# Schematic_Rev1.net
KiCad netlist of a schematic drawn in Altium Designer
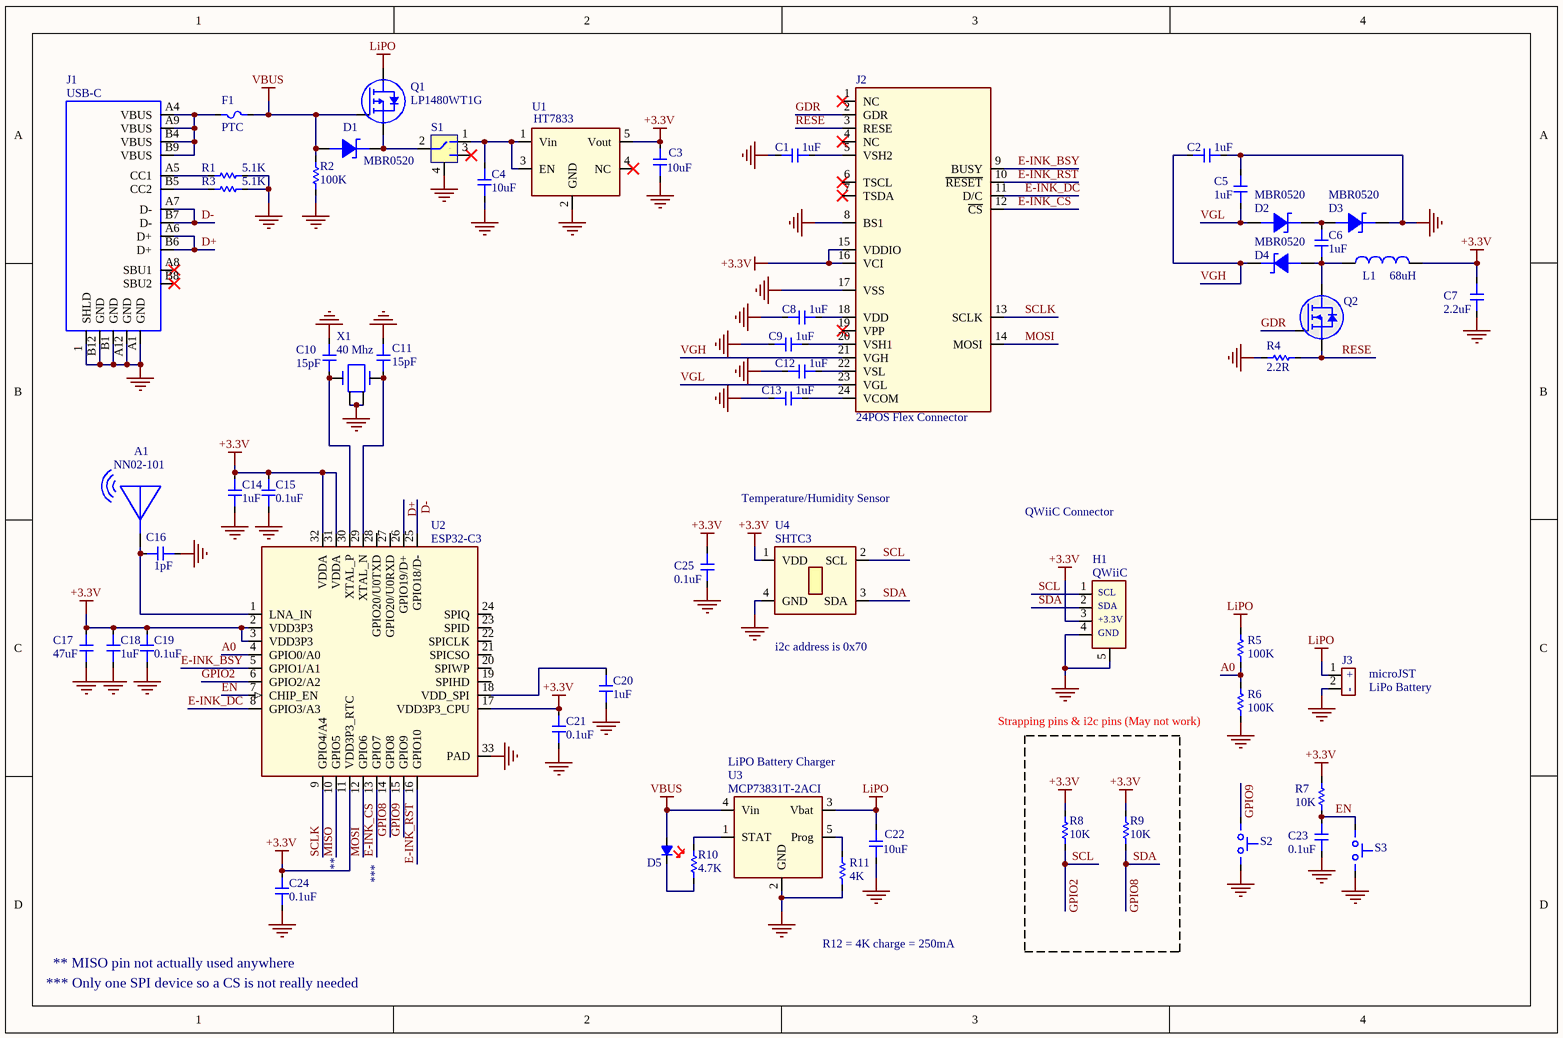
[diagram p0: Schematic_Rev1.SchDoc]

(export (version "E")
  (design (tool "Eeschema 10.0.6"))
  (components
    (comp (ref "A1")
      (value "NN02-101")
      (footprint "NN02-101")
      (description "Antenna Chip 2.4Gig")
      (fields (field (name "MANUFACTURER") "Ignion"))
      (libsource (lib "MAR") (part "NN02-101"))
    )
    (comp (ref "C1")
      (value "1uF")
      (footprint "CAPC1005X56N")
      (description "CAP 1uF 0402")
      (libsource (lib "MAR") (part "CAP_0402"))
    )
    (comp (ref "C2")
      (value "1uF")
      (footprint "CAPC1005X56N")
      (description "CAP 1uF 0402")
      (libsource (lib "MAR") (part "CAP_0402"))
    )
    (comp (ref "C3")
      (value "10uF")
      (footprint "CAPC2012X140N")
      (description "CAP 10uF 0805")
      (libsource (lib "MAR") (part "CAP_0805"))
    )
    (comp (ref "C4")
      (value "10uF")
      (footprint "CAPC2012X140N")
      (description "CAP 10uF 0805")
      (libsource (lib "MAR") (part "CAP_0805"))
    )
    (comp (ref "C5")
      (value "1uF")
      (footprint "CAPC1005X56N")
      (description "CAP 1uF 0402")
      (libsource (lib "MAR") (part "CAP_0402"))
    )
    (comp (ref "C6")
      (value "1uF")
      (footprint "CAPC1005X56N")
      (description "CAP 1uF 0402")
      (libsource (lib "MAR") (part "CAP_0402"))
    )
    (comp (ref "C7")
      (value "2.2uF")
      (footprint "CAPC1608X09L")
      (description "CAP 2.2uF 0603")
      (libsource (lib "MAR") (part "CAP_0402"))
    )
    (comp (ref "C8")
      (value "1uF")
      (footprint "CAPC1005X56N")
      (description "CAP 1uF 0402")
      (libsource (lib "MAR") (part "CAP_0402"))
    )
    (comp (ref "C9")
      (value "1uF")
      (footprint "CAPC1005X56N")
      (description "CAP 1uF 0402")
      (libsource (lib "MAR") (part "CAP_0402"))
    )
    (comp (ref "C10")
      (value "15pF")
      (footprint "CAPC1005X56N")
      (description "CAP 15pF 0402")
      (libsource (lib "MAR") (part "CAP_0402"))
    )
    (comp (ref "C11")
      (value "15pF")
      (footprint "CAPC1005X56N")
      (description "CAP 15pF 0402")
      (libsource (lib "MAR") (part "CAP_0402"))
    )
    (comp (ref "C12")
      (value "1uF")
      (footprint "CAPC1005X56N")
      (description "CAP 1uF 0402")
      (libsource (lib "MAR") (part "CAP_0402"))
    )
    (comp (ref "C13")
      (value "1uF")
      (footprint "CAPC1005X56N")
      (description "CAP 1uF 0402")
      (libsource (lib "MAR") (part "CAP_0402"))
    )
    (comp (ref "C14")
      (value "1uF")
      (footprint "CAPC1005X56N")
      (description "CAP 1uF 0402")
      (libsource (lib "MAR") (part "CAP_0402"))
    )
    (comp (ref "C15")
      (value "0.1uF")
      (footprint "CAPC1005X56N")
      (description "CAP 0.1uF 0402")
      (libsource (lib "MAR") (part "CAP_0402"))
    )
    (comp (ref "C16")
      (value "1pF")
      (footprint "CAPC1005X56N")
      (description "CAP 1pF 0402")
      (libsource (lib "MAR") (part "CAP_0402"))
    )
    (comp (ref "C17")
      (value "47uF")
      (footprint "CAPC3225X160N")
      (description "CAP 47uF 1210")
      (libsource (lib "MAR") (part "CAP_0402"))
    )
    (comp (ref "C18")
      (value "1uF")
      (footprint "CAPC1005X56N")
      (description "CAP 1uF 0402")
      (libsource (lib "MAR") (part "CAP_0402"))
    )
    (comp (ref "C19")
      (value "0.1uF")
      (footprint "CAPC1005X56N")
      (description "CAP 0.1uF 0402")
      (libsource (lib "MAR") (part "CAP_0402"))
    )
    (comp (ref "C20")
      (value "1uF")
      (footprint "CAPC1005X56N")
      (description "CAP 1uF 0402")
      (libsource (lib "MAR") (part "CAP_0402"))
    )
    (comp (ref "C21")
      (value "0.1uF")
      (footprint "CAPC1005X56N")
      (description "CAP 0.1uF 0402")
      (libsource (lib "MAR") (part "CAP_0402"))
    )
    (comp (ref "C22")
      (value "10uF")
      (footprint "CAPC2012X140N")
      (description "CAP 10uF 0805")
      (libsource (lib "MAR") (part "CAP_0805"))
    )
    (comp (ref "C23")
      (value "0.1uF")
      (footprint "CAPC1005X56N")
      (description "CAP 0.1uF 0402")
      (libsource (lib "MAR") (part "CAP_0402"))
    )
    (comp (ref "C24")
      (value "0.1uF")
      (footprint "CAPC1005X56N")
      (description "CAP 0.1uF 0402")
      (libsource (lib "MAR") (part "CAP_0402"))
    )
    (comp (ref "C25")
      (value "0.1uF")
      (footprint "CAPC1005X56N")
      (description "CAP 0.1uF 0402")
      (libsource (lib "MAR") (part "CAP_0402"))
    )
    (comp (ref "D1")
      (value "MBR0520")
      (footprint "SOD123")
      (description "DIODE SCHOTTKY 20V 500MA SOD-123")
      (fields (field (name "MANUFACTURER") "Micro") (field (name "PART_NUMBER") "C78746"))
      (libsource (lib "MAR") (part "MBR0520-TP"))
    )
    (comp (ref "D2")
      (value "MBR0520")
      (footprint "SOD123")
      (description "DIODE SCHOTTKY 20V 500MA SOD-123")
      (fields (field (name "MANUFACTURER") "Micro") (field (name "PART_NUMBER") "C78746"))
      (libsource (lib "MAR") (part "MBR0520-TP"))
    )
    (comp (ref "D3")
      (value "MBR0520")
      (footprint "SOD123")
      (description "DIODE SCHOTTKY 20V 500MA SOD-123")
      (fields (field (name "MANUFACTURER") "Micro") (field (name "PART_NUMBER") "C78746"))
      (libsource (lib "MAR") (part "MBR0520-TP"))
    )
    (comp (ref "D4")
      (value "MBR0520")
      (footprint "SOD123")
      (description "DIODE SCHOTTKY 20V 500MA SOD-123")
      (fields (field (name "MANUFACTURER") "Micro") (field (name "PART_NUMBER") "C78746"))
      (libsource (lib "MAR") (part "MBR0520-TP"))
    )
    (comp (ref "D5")
      (value "Red Led")
      (footprint "LED1005X40N-Red")
      (description "LED Red 0402")
      (fields (field (name "PART_NUMBER") "C364556") (field (name "MANUFACTURER") "Lite-On"))
      (libsource (lib "MAR") (part "LED_0402_SMALL_Red"))
    )
    (comp (ref "F1")
      (value "TLC-PSMD050")
      (footprint "PTC2012X70L")
      (description "PTC FUSE 500mA hold, 1A trip")
      (fields (field (name "MANUFACTURER") "TLC") (field (name "PART_NUMBER") "C261942"))
      (libsource (lib "MAR") (part "PTC_FUSE"))
    )
    (comp (ref "H1")
      (value "QWiiC")
      (footprint "SM04B-SRSS-TB")
      (description "CONN HEADER 4POS .100 R/A QWIIC")
      (fields (field (name "MANUFACTURER") "JST") (field (name "PART_NUMBER") "PRT-14417"))
      (libsource (lib "MAR") (part "SM04B-SRSS-TB"))
    )
    (comp (ref "J1")
      (value "USB-C")
      (footprint "TYPE-C-31-M-12")
      (description "CONN RECPT USB-C")
      (fields (field (name "MANUFACTURER") "KHE") (field (name "PART_NUMBER") "C165948"))
      (libsource (lib "MAR") (part "USB-C"))
    )
    (comp (ref "J2")
      (value "24POS Flex Connector")
      (footprint "687124182122")
      (description "CONN FFC TOP/BOT 24POS 0.50MM R/A")
      (fields (field (name "MANUFACTURER") "Wurth") (field (name "PART_NUMBER") "687124182122"))
      (libsource (lib "MAR") (part "687124182122"))
    )
    (comp (ref "J3")
      (value "CON2")
      (footprint "JST_Micro_2PIN")
      (description "JST MIcro CONN 2POS")
      (libsource (lib "MAR") (part "JST_Micro_CONN_2PIN"))
    )
    (comp (ref "L1")
      (value "68uH")
      (footprint "INDUCTOR, 4mmX4mm")
      (description "INDUCTOR 68uH 20% 4mmx4mm")
      (fields (field (name "PART_NUMBER") "C135265") (field (name "MANUFACTURER") "SXN"))
      (libsource (lib "MAR") (part "68uH"))
    )
    (comp (ref "Q1")
      (value "LP1480WT1G")
      (footprint "SC-70")
      (description "MOSFET P-CH 20V 1.4A SC-70")
      (fields (field (name "MANUFACTURER") "LRC") (field (name "PART_NUMBER") "C172434"))
      (libsource (lib "MAR") (part "LP1480WT1G"))
    )
    (comp (ref "Q2")
      (value "~")
      (footprint "SOT95P240X110-3N")
      (description "MOSFET N-CH 60V 300MA SOT-23")
      (fields (field (name "MANUFACTURER") "Vishay Siliconix") (field (name "PART_NUMBER") "2N7002K-T1-E3"))
      (libsource (lib "MAR") (part "2N7002K-T1-E3"))
    )
    (comp (ref "R1")
      (value "5.1K")
      (footprint "RESC1005X40L (0402 FOOTPRINT)")
      (description "RES 5.1K 0402")
      (libsource (lib "MAR") (part "RES_0402"))
    )
    (comp (ref "R2")
      (value "100K")
      (footprint "RESC1005X40L (0402 FOOTPRINT)")
      (description "RES 100K 0402")
      (libsource (lib "MAR") (part "RES_0402"))
    )
    (comp (ref "R3")
      (value "5.1K")
      (footprint "RESC1005X40L (0402 FOOTPRINT)")
      (description "RES 5.1K 0402")
      (libsource (lib "MAR") (part "RES_0402"))
    )
    (comp (ref "R4")
      (value "2.2R")
      (footprint "RESC1005X40L (0402 FOOTPRINT)")
      (description "RES 2.2R 0402")
      (libsource (lib "MAR") (part "RES_0402"))
    )
    (comp (ref "R5")
      (value "100K")
      (footprint "RESC1005X40L (0402 FOOTPRINT)")
      (description "RES 100K 0402")
      (libsource (lib "MAR") (part "RES_0402"))
    )
    (comp (ref "R6")
      (value "100K")
      (footprint "RESC1005X40L (0402 FOOTPRINT)")
      (description "RES 100K 0402")
      (libsource (lib "MAR") (part "RES_0402"))
    )
    (comp (ref "R7")
      (value "10K")
      (footprint "RESC1005X40L (0402 FOOTPRINT)")
      (description "RES 10K 0402")
      (libsource (lib "MAR") (part "RES_0402"))
    )
    (comp (ref "R8")
      (value "10K")
      (footprint "RESC1005X40L (0402 FOOTPRINT)")
      (description "RES 10K 0402")
      (libsource (lib "MAR") (part "RES_0402"))
    )
    (comp (ref "R9")
      (value "10K")
      (footprint "RESC1005X40L (0402 FOOTPRINT)")
      (description "RES 10K 0402")
      (libsource (lib "MAR") (part "RES_0402"))
    )
    (comp (ref "R10")
      (value "4.7K")
      (footprint "RESC1005X40L (0402 FOOTPRINT)")
      (description "RES 4.7K 0402")
      (libsource (lib "MAR") (part "RES_0402"))
    )
    (comp (ref "R11")
      (value "4K")
      (footprint "RESC1005X40L (0402 FOOTPRINT)")
      (description "RES 4K 0402")
      (libsource (lib "MAR") (part "RES_0402"))
    )
    (comp (ref "S1")
      (value "SWITCH SLIDE")
      (footprint "K3-1296S-E1")
      (description "SWITCH SLIDE SMD")
      (fields (field (name "MANUFACTURER") "Korean Hroparts Elec") (field (name "PART_NUMBER") "K3-1296S-E1"))
      (libsource (lib "MAR") (part "K3-1296S-E1"))
    )
    (comp (ref "S2")
      (value "~")
      (footprint "TS-1088R-02526")
      (description "Tactile Micro Switch")
      (fields (field (name "PART_NUMBER") "C455281") (field (name "MANUFACTURER") "XUNPU"))
      (libsource (lib "MAR") (part "TS-1088R-02526"))
    )
    (comp (ref "S3")
      (value "~")
      (footprint "TS-1088R-02526")
      (description "Tactile Micro Switch")
      (fields (field (name "PART_NUMBER") "C455281") (field (name "MANUFACTURER") "XUNPU"))
      (libsource (lib "MAR") (part "TS-1088R-02526"))
    )
    (comp (ref "U1")
      (value "HT7833")
      (footprint "SOT95P280X144-5N")
      (description "IC LDO 3.3V 0.5A SOT23-5")
      (fields (field (name "MANUFACTURER") "Holtek") (field (name "PART_NUMBER") "C164106"))
      (libsource (lib "MAR") (part "HT7833"))
    )
    (comp (ref "U2")
      (value "ESP32-C3")
      (footprint "VFQFN-32 -ESP32-C3")
      (description "WIFI/Bluetooth, VFQFN-32")
      (fields (field (name "MANUFACTURER") "Espressif") (field (name "PART_NUMBER") "C529594"))
      (libsource (lib "MAR") (part "ESP32-C3"))
    )
    (comp (ref "U3")
      (value "MCP73831T-2ACI")
      (footprint "SOT95P280X144-5N")
      (description "Charger IC Lithium-Ion/Polymer SOT23-5")
      (fields (field (name "MANUFACTURER") "Microchip") (field (name "PART_NUMBER") "MCP73831T-2ACI/OT"))
      (libsource (lib "MAR") (part "MCP73831T-2ACI/OT"))
    )
    (comp (ref "U4")
      (value "SHTC3")
      (footprint "DFN-4 (2.0mm X 2.0mm)")
      (description "Humidity/Temperature Sensor")
      (fields (field (name "MANUFACTURER") "Sensirion") (field (name "PART_NUMBER") "SHTC3"))
      (libsource (lib "MAR") (part "SHTC3"))
    )
    (comp (ref "X1")
      (value "40 Mhz")
      (footprint "OSC20X16")
      (description "CRYSTAL 40MHZ 10PF SMD")
      (fields (field (name "PART_NUMBER") "ECS-400-10-37B2-CKM") (field (name "MANUFACTURER") "ECS"))
      (libsource (lib "MAR") (part "40Mhz"))
    )
  )
  (nets
    (net (code "1") (name "+3.3V") (class "Default")
      (node (ref "C14") (pin "1") (pintype "passive"))
      (node (ref "C15") (pin "1") (pintype "passive"))
      (node (ref "C17") (pin "1") (pintype "passive"))
      (node (ref "C18") (pin "1") (pintype "passive"))
      (node (ref "C19") (pin "1") (pintype "passive"))
      (node (ref "C21") (pin "1") (pintype "passive"))
      (node (ref "C24") (pin "1") (pintype "passive"))
      (node (ref "C25") (pin "1") (pintype "passive"))
      (node (ref "C3") (pin "1") (pintype "passive"))
      (node (ref "C7") (pin "1") (pintype "passive"))
      (node (ref "H1") (pin "3") (pintype "passive"))
      (node (ref "J2") (pin "15") (pinfunction "VDDIO_15") (pintype "power_in"))
      (node (ref "J2") (pin "16") (pinfunction "VCI_16") (pintype "power_in"))
      (node (ref "L1") (pin "2") (pinfunction "2_2") (pintype "passive"))
      (node (ref "R7") (pin "1") (pintype "passive"))
      (node (ref "R8") (pin "2") (pintype "passive"))
      (node (ref "R9") (pin "2") (pintype "passive"))
      (node (ref "U1") (pin "5") (pinfunction "Vout_5") (pintype "passive"))
      (node (ref "U2") (pin "11") (pinfunction "VDD3P3_RTC_11") (pintype "power_in"))
      (node (ref "U2") (pin "17") (pinfunction "VDD3P3_CPU_17") (pintype "power_in"))
      (node (ref "U2") (pin "2") (pinfunction "VDD3P3_2") (pintype "power_in"))
      (node (ref "U2") (pin "3") (pinfunction "VDD3P3_3") (pintype "power_in"))
      (node (ref "U2") (pin "31") (pinfunction "VDDA_31") (pintype "power_in"))
      (node (ref "U2") (pin "32") (pinfunction "VDDA_32") (pintype "power_in"))
      (node (ref "U4") (pin "1") (pinfunction "VDD_1") (pintype "power_in"))
    )
    (net (code "2") (name "/A0") (class "Default")
      (node (ref "R5") (pin "1") (pintype "passive"))
      (node (ref "R6") (pin "2") (pintype "passive"))
      (node (ref "U2") (pin "4") (pinfunction "GPIO0/A0_4") (pintype "passive"))
    )
    (net (code "3") (name "/D+") (class "Default")
      (node (ref "J1") (pin "A6") (pinfunction "D+_A6") (pintype "power_in"))
      (node (ref "J1") (pin "B6") (pinfunction "D+_B6") (pintype "power_in"))
      (node (ref "U2") (pin "26") (pinfunction "GPIO19/D+_26") (pintype "passive"))
    )
    (net (code "4") (name "/D-") (class "Default")
      (node (ref "J1") (pin "A7") (pinfunction "D-_A7") (pintype "power_in"))
      (node (ref "J1") (pin "B7") (pinfunction "D-_B7") (pintype "power_in"))
      (node (ref "U2") (pin "25") (pinfunction "GPIO18/D-_25") (pintype "passive"))
    )
    (net (code "5") (name "/E-INK_BSY") (class "Default")
      (node (ref "J2") (pin "9") (pinfunction "BUSY_9") (pintype "passive"))
      (node (ref "U2") (pin "5") (pinfunction "GPIO1/A1_5") (pintype "passive"))
    )
    (net (code "6") (name "/E-INK_CS") (class "Default")
      (node (ref "J2") (pin "12") (pinfunction "~{CS}_12") (pintype "passive"))
      (node (ref "U2") (pin "13") (pinfunction "GPIO7_13") (pintype "passive"))
    )
    (net (code "7") (name "/E-INK_DC") (class "Default")
      (node (ref "J2") (pin "11") (pinfunction "D/C_11") (pintype "passive"))
      (node (ref "U2") (pin "8") (pinfunction "GPIO3/A3_8") (pintype "passive"))
    )
    (net (code "8") (name "/E-INK_RST") (class "Default")
      (node (ref "J2") (pin "10") (pinfunction "~{RESET}_10") (pintype "passive"))
      (node (ref "U2") (pin "16") (pinfunction "GPIO10_16") (pintype "passive"))
    )
    (net (code "9") (name "/EN") (class "Default")
      (node (ref "C23") (pin "1") (pintype "passive"))
      (node (ref "R7") (pin "2") (pintype "passive"))
      (node (ref "S3") (pin "1") (pinfunction "A_1") (pintype "passive"))
      (node (ref "U2") (pin "7") (pinfunction "CHIP_EN_7") (pintype "input"))
    )
    (net (code "10") (name "/GDR") (class "Default")
      (node (ref "J2") (pin "2") (pinfunction "GDR_2") (pintype "passive"))
      (node (ref "Q2") (pin "1") (pinfunction "G_1") (pintype "passive"))
    )
    (net (code "11") (name "/GPIO2") (class "Default")
      (node (ref "H1") (pin "1") (pintype "passive"))
      (node (ref "R8") (pin "1") (pintype "passive"))
      (node (ref "U2") (pin "6") (pinfunction "GPIO2/A2_6") (pintype "passive"))
      (node (ref "U4") (pin "2") (pinfunction "SCL_2") (pintype "passive"))
    )
    (net (code "12") (name "/GPIO8") (class "Default")
      (node (ref "H1") (pin "2") (pintype "passive"))
      (node (ref "R9") (pin "1") (pintype "passive"))
      (node (ref "U2") (pin "14") (pinfunction "GPIO8_14") (pintype "passive"))
      (node (ref "U4") (pin "3") (pinfunction "SDA_3") (pintype "passive"))
    )
    (net (code "13") (name "/GPIO9") (class "Default")
      (node (ref "S2") (pin "1") (pinfunction "A_1") (pintype "passive"))
      (node (ref "U2") (pin "15") (pinfunction "GPIO9_15") (pintype "passive"))
    )
    (net (code "14") (name "/MISO") (class "Default")
      (node (ref "U2") (pin "10") (pinfunction "GPIO5_10") (pintype "passive"))
    )
    (net (code "15") (name "/MOSI") (class "Default")
      (node (ref "J2") (pin "14") (pinfunction "MOSI_14") (pintype "passive"))
      (node (ref "U2") (pin "12") (pinfunction "GPIO6_12") (pintype "passive"))
    )
    (net (code "16") (name "/RESE") (class "Default")
      (node (ref "J2") (pin "3") (pinfunction "RESE_3") (pintype "passive"))
      (node (ref "Q2") (pin "2") (pinfunction "S_2") (pintype "passive"))
      (node (ref "R4") (pin "1") (pintype "passive"))
    )
    (net (code "17") (name "/SCLK") (class "Default")
      (node (ref "J2") (pin "13") (pinfunction "SCLK_13") (pintype "passive"))
      (node (ref "U2") (pin "9") (pinfunction "GPIO4/A4_9") (pintype "passive"))
    )
    (net (code "18") (name "/VGH") (class "Default")
      (node (ref "C2") (pin "1") (pintype "passive"))
      (node (ref "D4") (pin "1") (pinfunction "Cathode_1") (pintype "passive"))
      (node (ref "J2") (pin "21") (pinfunction "VGH_21") (pintype "passive"))
    )
    (net (code "19") (name "/VGL") (class "Default")
      (node (ref "C5") (pin "2") (pintype "passive"))
      (node (ref "D2") (pin "2") (pinfunction "Annode_2") (pintype "passive"))
      (node (ref "J2") (pin "23") (pinfunction "VGL_23") (pintype "passive"))
    )
    (net (code "20") (name "GND") (class "Default")
      (node (ref "C1") (pin "1") (pintype "passive"))
      (node (ref "C10") (pin "1") (pintype "passive"))
      (node (ref "C11") (pin "1") (pintype "passive"))
      (node (ref "C12") (pin "1") (pintype "passive"))
      (node (ref "C13") (pin "1") (pintype "passive"))
      (node (ref "C14") (pin "2") (pintype "passive"))
      (node (ref "C15") (pin "2") (pintype "passive"))
      (node (ref "C16") (pin "2") (pintype "passive"))
      (node (ref "C17") (pin "2") (pintype "passive"))
      (node (ref "C18") (pin "2") (pintype "passive"))
      (node (ref "C19") (pin "2") (pintype "passive"))
      (node (ref "C2") (pin "2") (pintype "passive"))
      (node (ref "C20") (pin "2") (pintype "passive"))
      (node (ref "C21") (pin "2") (pintype "passive"))
      (node (ref "C22") (pin "2") (pintype "passive"))
      (node (ref "C23") (pin "2") (pintype "passive"))
      (node (ref "C24") (pin "2") (pintype "passive"))
      (node (ref "C25") (pin "2") (pintype "passive"))
      (node (ref "C3") (pin "2") (pintype "passive"))
      (node (ref "C4") (pin "2") (pintype "passive"))
      (node (ref "C5") (pin "1") (pintype "passive"))
      (node (ref "C7") (pin "2") (pintype "passive"))
      (node (ref "C8") (pin "1") (pintype "passive"))
      (node (ref "C9") (pin "1") (pintype "passive"))
      (node (ref "D3") (pin "1") (pinfunction "Cathode_1") (pintype "passive"))
      (node (ref "H1") (pin "4") (pintype "passive"))
      (node (ref "H1") (pin "5") (pintype "passive"))
      (node (ref "J1") (pin "1") (pinfunction "SHLD_1") (pintype "power_in"))
      (node (ref "J1") (pin "A1") (pinfunction "GND_A1") (pintype "power_in"))
      (node (ref "J1") (pin "A12") (pinfunction "GND_A12") (pintype "power_in"))
      (node (ref "J1") (pin "B1") (pinfunction "GND_B1") (pintype "power_in"))
      (node (ref "J1") (pin "B12") (pinfunction "GND_B12") (pintype "passive"))
      (node (ref "J2") (pin "17") (pinfunction "VSS_17") (pintype "power_in"))
      (node (ref "J2") (pin "8") (pinfunction "BS1_8") (pintype "passive"))
      (node (ref "J3") (pin "2") (pintype "passive"))
      (node (ref "R1") (pin "1") (pintype "passive"))
      (node (ref "R11") (pin "1") (pintype "passive"))
      (node (ref "R2") (pin "2") (pintype "passive"))
      (node (ref "R3") (pin "1") (pintype "passive"))
      (node (ref "R4") (pin "2") (pintype "passive"))
      (node (ref "R6") (pin "1") (pintype "passive"))
      (node (ref "S1") (pin "4") (pinfunction "4_4") (pintype "passive"))
      (node (ref "S2") (pin "2") (pinfunction "B_2") (pintype "passive"))
      (node (ref "S3") (pin "2") (pinfunction "B_2") (pintype "passive"))
      (node (ref "U1") (pin "2") (pinfunction "GND_2") (pintype "power_in"))
      (node (ref "U2") (pin "33") (pinfunction "PAD_33") (pintype "power_in"))
      (node (ref "U3") (pin "2") (pinfunction "GND_2") (pintype "power_in"))
      (node (ref "U4") (pin "4") (pinfunction "GND_4") (pintype "power_in"))
      (node (ref "X1") (pin "2") (pinfunction "2_2") (pintype "power_in"))
      (node (ref "X1") (pin "4") (pinfunction "4_4") (pintype "power_in"))
    )
    (net (code "21") (name "LiPO") (class "Default")
      (node (ref "C22") (pin "1") (pintype "passive"))
      (node (ref "J3") (pin "1") (pintype "passive"))
      (node (ref "Q1") (pin "3") (pinfunction "D_3") (pintype "passive"))
      (node (ref "R5") (pin "2") (pintype "passive"))
      (node (ref "U3") (pin "3") (pinfunction "Vbat_3") (pintype "passive"))
    )
    (net (code "22") (name "Net-(D1-Cathode)") (class "Default")
      (node (ref "D1") (pin "1") (pinfunction "Cathode_1") (pintype "passive"))
      (node (ref "Q1") (pin "2") (pinfunction "S_2") (pintype "passive"))
      (node (ref "S1") (pin "2") (pinfunction "2_2") (pintype "passive"))
    )
    (net (code "23") (name "Net-(D2-Cathode)") (class "Default")
      (node (ref "C6") (pin "1") (pintype "passive"))
      (node (ref "D2") (pin "1") (pinfunction "Cathode_1") (pintype "passive"))
      (node (ref "D3") (pin "2") (pinfunction "Annode_2") (pintype "passive"))
    )
    (net (code "24") (name "Net-(D4-Annode)") (class "Default")
      (node (ref "C6") (pin "2") (pintype "passive"))
      (node (ref "D4") (pin "2") (pinfunction "Annode_2") (pintype "passive"))
      (node (ref "L1") (pin "1") (pinfunction "1_1") (pintype "passive"))
      (node (ref "Q2") (pin "3") (pinfunction "D_3") (pintype "passive"))
    )
    (net (code "25") (name "Net-(D5-Pad1)") (class "Default")
      (node (ref "D5") (pin "1") (pintype "passive"))
      (node (ref "R10") (pin "1") (pintype "passive"))
    )
    (net (code "26") (name "Net-(F1-Pad2)") (class "Default")
      (node (ref "F1") (pin "2") (pintype "passive"))
      (node (ref "J1") (pin "A4") (pinfunction "VBUS_A4") (pintype "passive"))
      (node (ref "J1") (pin "A9") (pinfunction "VBUS_A9") (pintype "power_in"))
      (node (ref "J1") (pin "B4") (pinfunction "VBUS_B4") (pintype "power_in"))
      (node (ref "J1") (pin "B9") (pinfunction "VBUS_B9") (pintype "passive"))
    )
    (net (code "27") (name "Net-(J1-CC1)") (class "Default")
      (node (ref "J1") (pin "A5") (pinfunction "CC1_A5") (pintype "power_in"))
      (node (ref "R1") (pin "2") (pintype "passive"))
    )
    (net (code "28") (name "Net-(J1-CC2)") (class "Default")
      (node (ref "J1") (pin "B5") (pinfunction "CC2_B5") (pintype "power_in"))
      (node (ref "R3") (pin "2") (pintype "passive"))
    )
    (net (code "29") (name "Net-(J2-VCOM)") (class "Default")
      (node (ref "C13") (pin "2") (pintype "passive"))
      (node (ref "J2") (pin "24") (pinfunction "VCOM_24") (pintype "passive"))
    )
    (net (code "30") (name "Net-(J2-VDD)") (class "Default")
      (node (ref "C8") (pin "2") (pintype "passive"))
      (node (ref "J2") (pin "18") (pinfunction "VDD_18") (pintype "power_in"))
    )
    (net (code "31") (name "Net-(J2-VSH1)") (class "Default")
      (node (ref "C9") (pin "2") (pintype "passive"))
      (node (ref "J2") (pin "20") (pinfunction "VSH1_20") (pintype "passive"))
    )
    (net (code "32") (name "Net-(J2-VSH2)") (class "Default")
      (node (ref "C1") (pin "2") (pintype "passive"))
      (node (ref "J2") (pin "5") (pinfunction "VSH2_5") (pintype "passive"))
    )
    (net (code "33") (name "Net-(J2-VSL)") (class "Default")
      (node (ref "C12") (pin "2") (pintype "passive"))
      (node (ref "J2") (pin "22") (pinfunction "VSL_22") (pintype "passive"))
    )
    (net (code "34") (name "Net-(U1-EN)") (class "Default")
      (node (ref "C4") (pin "1") (pintype "passive"))
      (node (ref "S1") (pin "1") (pinfunction "1_1") (pintype "passive"))
      (node (ref "U1") (pin "1") (pinfunction "Vin_1") (pintype "passive"))
      (node (ref "U1") (pin "3") (pinfunction "EN_3") (pintype "passive"))
    )
    (net (code "35") (name "Net-(U2-LNA_IN)") (class "Default")
      (node (ref "A1") (pin "1") (pintype "passive"))
      (node (ref "C16") (pin "1") (pintype "passive"))
      (node (ref "U2") (pin "1") (pinfunction "LNA_IN_1") (pintype "passive"))
    )
    (net (code "36") (name "Net-(U2-VDD_SPI)") (class "Default")
      (node (ref "C20") (pin "1") (pintype "passive"))
      (node (ref "U2") (pin "18") (pinfunction "VDD_SPI_18") (pintype "power_in"))
    )
    (net (code "37") (name "Net-(U2-XTAL_N)") (class "Default")
      (node (ref "C11") (pin "2") (pintype "passive"))
      (node (ref "U2") (pin "29") (pinfunction "XTAL_N_29") (pintype "passive"))
      (node (ref "X1") (pin "3") (pinfunction "3_3") (pintype "passive"))
    )
    (net (code "38") (name "Net-(U2-XTAL_P)") (class "Default")
      (node (ref "C10") (pin "2") (pintype "passive"))
      (node (ref "U2") (pin "30") (pinfunction "XTAL_P_30") (pintype "passive"))
      (node (ref "X1") (pin "1") (pinfunction "1_1") (pintype "passive"))
    )
    (net (code "39") (name "Net-(U3-Prog)") (class "Default")
      (node (ref "R11") (pin "2") (pintype "passive"))
      (node (ref "U3") (pin "5") (pinfunction "Prog_5") (pintype "passive"))
    )
    (net (code "40") (name "Net-(U3-STAT)") (class "Default")
      (node (ref "R10") (pin "2") (pintype "passive"))
      (node (ref "U3") (pin "1") (pinfunction "STAT_1") (pintype "passive"))
    )
    (net (code "41") (name "VBUS") (class "Default")
      (node (ref "D1") (pin "2") (pinfunction "Annode_2") (pintype "passive"))
      (node (ref "D5") (pin "2") (pintype "passive"))
      (node (ref "F1") (pin "1") (pintype "passive"))
      (node (ref "Q1") (pin "1") (pinfunction "G_1") (pintype "passive"))
      (node (ref "R2") (pin "1") (pintype "passive"))
      (node (ref "U3") (pin "4") (pinfunction "Vin_4") (pintype "passive"))
    )
    (net (code "42") (name "unconnected-(J1-SBU1-PadA8)") (class "Default")
      (node (ref "J1") (pin "A8") (pinfunction "SBU1_A8") (pintype "power_in+no_connect"))
    )
    (net (code "43") (name "unconnected-(J1-SBU2-PadB8)") (class "Default")
      (node (ref "J1") (pin "B8") (pinfunction "SBU2_B8") (pintype "power_in+no_connect"))
    )
    (net (code "44") (name "unconnected-(J2-NC-Pad1)") (class "Default")
      (node (ref "J2") (pin "1") (pinfunction "NC_1") (pintype "passive+no_connect"))
    )
    (net (code "45") (name "unconnected-(J2-NC-Pad4)") (class "Default")
      (node (ref "J2") (pin "4") (pinfunction "NC_4") (pintype "passive+no_connect"))
    )
    (net (code "46") (name "unconnected-(J2-TSCL-Pad6)") (class "Default")
      (node (ref "J2") (pin "6") (pinfunction "TSCL_6") (pintype "passive+no_connect"))
    )
    (net (code "47") (name "unconnected-(J2-TSDA-Pad7)") (class "Default")
      (node (ref "J2") (pin "7") (pinfunction "TSDA_7") (pintype "passive+no_connect"))
    )
    (net (code "48") (name "unconnected-(J2-VPP-Pad19)") (class "Default")
      (node (ref "J2") (pin "19") (pinfunction "VPP_19") (pintype "passive+no_connect"))
    )
    (net (code "49") (name "unconnected-(S1-Pad3)") (class "Default")
      (node (ref "S1") (pin "3") (pinfunction "3_3") (pintype "passive+no_connect"))
    )
    (net (code "50") (name "unconnected-(U1-NC-Pad4)") (class "Default")
      (node (ref "U1") (pin "4") (pinfunction "NC_4") (pintype "passive+no_connect"))
    )
    (net (code "51") (name "unconnected-(U2-GPIO20{slash}U0RXD-Pad27)") (class "Default")
      (node (ref "U2") (pin "27") (pinfunction "GPIO20/U0RXD_27") (pintype "passive"))
    )
    (net (code "52") (name "unconnected-(U2-GPIO20{slash}U0TXD-Pad28)") (class "Default")
      (node (ref "U2") (pin "28") (pinfunction "GPIO20/U0TXD_28") (pintype "passive"))
    )
    (net (code "53") (name "unconnected-(U2-SPICLK-Pad22)") (class "Default")
      (node (ref "U2") (pin "22") (pinfunction "SPICLK_22") (pintype "passive"))
    )
    (net (code "54") (name "unconnected-(U2-SPICSO-Pad21)") (class "Default")
      (node (ref "U2") (pin "21") (pinfunction "SPICSO_21") (pintype "passive"))
    )
    (net (code "55") (name "unconnected-(U2-SPID-Pad23)") (class "Default")
      (node (ref "U2") (pin "23") (pinfunction "SPID_23") (pintype "passive"))
    )
    (net (code "56") (name "unconnected-(U2-SPIHD-Pad19)") (class "Default")
      (node (ref "U2") (pin "19") (pinfunction "SPIHD_19") (pintype "passive"))
    )
    (net (code "57") (name "unconnected-(U2-SPIQ-Pad24)") (class "Default")
      (node (ref "U2") (pin "24") (pinfunction "SPIQ_24") (pintype "passive"))
    )
    (net (code "58") (name "unconnected-(U2-SPIWP-Pad20)") (class "Default")
      (node (ref "U2") (pin "20") (pinfunction "SPIWP_20") (pintype "passive"))
    )
  )
)
